# DEPRECATED-lvd.net
KiCad netlist of a schematic drawn in Altium Designer
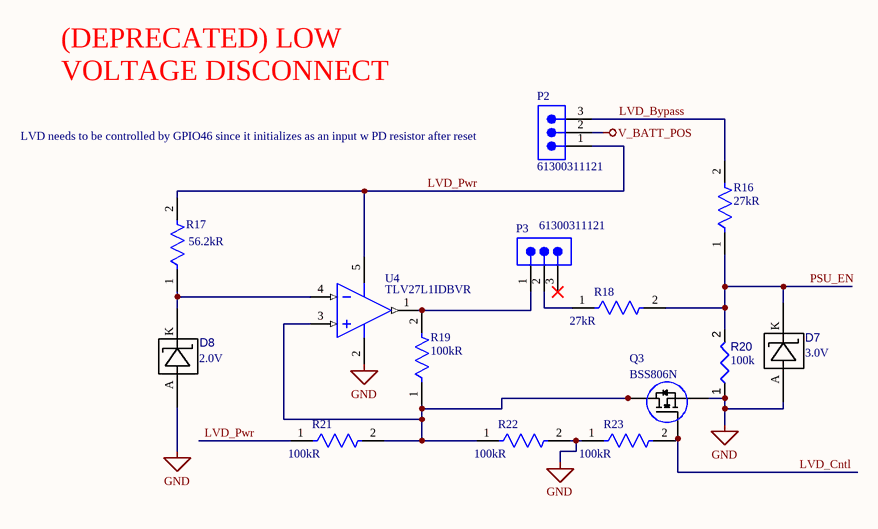
[diagram p0: DEPRECATED-lvd.SchDoc]

(export (version "E")
  (design (tool "Eeschema 10.0.6"))
  (components
    (comp (ref "D7")
      (value "BZX58550-C3V0-QX")
      (footprint "SOD523 (SC-79)")
      (description "Diode Zener Single 3V 5% 300mW 2-Pin SOD-523 T/R")
      (fields (field (name "NOMINAL VOLTAGE") "3.0V"))
      (libsource (lib "Camosun College") (part "Zener - SOD523"))
    )
    (comp (ref "D8")
      (value "BZX58550-C2V0-QX")
      (footprint "SOD523 (SC-79)")
      (description "Diode Zener Single 2V 5% 300mW 2-Pin SOD-523 T/R")
      (fields (field (name "NOMINAL VOLTAGE") "2.0V"))
      (libsource (lib "Camosun College") (part "Zener - SOD523"))
    )
    (comp (ref "P2")
      (value "61300311121")
      (footprint "61300311121")
      (libsource (lib "Camosun College") (part "Header_Male_1R_03P"))
    )
    (comp (ref "P3")
      (value "61300311121")
      (footprint "61300311121")
      (libsource (lib "Camosun College") (part "Header_Male_1R_03P"))
    )
    (comp (ref "Q3")
      (value "BSS806N")
      (footprint "INF-PG-SOT23_M")
      (libsource (lib "Camosun College") (part "MOSFET-N_CHANNEL"))
    )
    (comp (ref "R16")
      (value "RMCF0805FT27K0")
      (footprint "FP-RMCF0805-IPC_A")
      (description "27kΩ ±1% 0.125W 0805 Thick Film Chip Resistor AEC-Q200 compliant")
      (fields (field (name "RESISTANCE") "27kR") (field (name "TOLERANCE") "1%"))
      (libsource (lib "Altium Content Vault") (part "1029c3af85768c4190bb7ad29bc67b5"))
    )
    (comp (ref "R17")
      (value "RMCF0805FT56K2")
      (footprint "FP-RMCF0805-IPC_A")
      (description "56.2kΩ ±1% 0.125W 0805 Thick Film Chip Resistor AEC-Q200 compliant")
      (fields (field (name "TOLERANCE") "1%") (field (name "RESISTANCE") "56.2kR"))
      (libsource (lib "Altium Content Vault") (part "1029c3af85768c4190bb7ad29bc67b5"))
    )
    (comp (ref "R18")
      (value "RMCF0805FT27K0")
      (footprint "FP-RMCF0805-IPC_A")
      (description "27kΩ ±1% 0.125W 0805 Thick Film Chip Resistor AEC-Q200 compliant")
      (fields (field (name "RESISTANCE") "27kR") (field (name "TOLERANCE") "1%"))
      (libsource (lib "Altium Content Vault") (part "1029c3af85768c4190bb7ad29bc67b5"))
    )
    (comp (ref "R19")
      (value "RMCF0805FG100K")
      (footprint "FP-RMCF0805-IPC_C")
      (description "100kΩ ±1% 0.125W 0805 Thick Film Chip Resistor AEC-Q200 compliant")
      (fields (field (name "RESISTANCE") "100kR") (field (name "TOLERANCE") "1%"))
      (libsource (lib "Altium Content Vault") (part "1029c3af85768c4190bb7ad29bc67b5"))
    )
    (comp (ref "R20")
      (value "100k")
      (footprint "RESC1608X55X25ML10T15")
      (description "Chip Resistor, 100 KOhm, +/- 1%, 0.1 W, -55 to 155 degC, 0603 (1608 Metric)")
      (fields (field (name "TOLERANCE") "1%") (field (name "POWER") "100mW"))
      (libsource (lib "Camosun College") (part "RES-2"))
    )
    (comp (ref "R21")
      (value "RMCF0805FG100K")
      (footprint "FP-RMCF0805-IPC_C")
      (description "100kΩ ±1% 0.125W 0805 Thick Film Chip Resistor AEC-Q200 compliant")
      (fields (field (name "RESISTANCE") "100kR") (field (name "TOLERANCE") "1%"))
      (libsource (lib "Altium Content Vault") (part "1029c3af85768c4190bb7ad29bc67b5"))
    )
    (comp (ref "R22")
      (value "RMCF0805FG100K")
      (footprint "FP-RMCF0805-IPC_C")
      (description "100kΩ ±1% 0.125W 0805 Thick Film Chip Resistor AEC-Q200 compliant")
      (fields (field (name "RESISTANCE") "100kR") (field (name "TOLERANCE") "1%"))
      (libsource (lib "Altium Content Vault") (part "1029c3af85768c4190bb7ad29bc67b5"))
    )
    (comp (ref "R23")
      (value "RMCF0805FG100K")
      (footprint "FP-RMCF0805-IPC_C")
      (description "100kΩ ±1% 0.125W 0805 Thick Film Chip Resistor AEC-Q200 compliant")
      (fields (field (name "RESISTANCE") "100kR") (field (name "TOLERANCE") "1%"))
      (libsource (lib "Altium Content Vault") (part "1029c3af85768c4190bb7ad29bc67b5"))
    )
    (comp (ref "U4")
      (value "TLV27L1IDBVR")
      (footprint "DBV0005A_L")
      (fields (field (name "MANUFACTURER") "Texas Instruments"))
      (libsource (lib "Altium Content Vault") (part "TI-TLV2XX1DBV5"))
    )
  )
  (nets
    (net (code "1") (name "/LVD_Bypass") (class "Default")
      (node (ref "P2") (pin "3") (pinfunction "3_3") (pintype "passive"))
      (node (ref "R16") (pin "2") (pinfunction "2_2") (pintype "passive"))
    )
    (net (code "2") (name "/LVD_Cntl") (class "Default")
      (node (ref "Q3") (pin "G") (pinfunction "G_G") (pintype "passive"))
      (node (ref "R23") (pin "2") (pinfunction "2_2") (pintype "passive"))
    )
    (net (code "3") (name "/LVD_Pwr") (class "Default")
      (node (ref "P2") (pin "1") (pinfunction "1_1") (pintype "passive"))
      (node (ref "R17") (pin "2") (pinfunction "2_2") (pintype "passive"))
      (node (ref "R21") (pin "1") (pinfunction "1_1") (pintype "passive"))
      (node (ref "U4") (pin "5") (pinfunction "VDD_5") (pintype "power_in"))
    )
    (net (code "4") (name "/PSU_EN") (class "Default")
      (node (ref "D7") (pin "K") (pinfunction "K_K") (pintype "passive"))
      (node (ref "R16") (pin "1") (pinfunction "1_1") (pintype "passive"))
      (node (ref "R18") (pin "2") (pinfunction "2_2") (pintype "passive"))
      (node (ref "R20") (pin "2") (pinfunction "2_2") (pintype "passive"))
    )
    (net (code "5") (name "GND") (class "Default")
      (node (ref "D7") (pin "A") (pinfunction "A_A") (pintype "passive"))
      (node (ref "D8") (pin "A") (pinfunction "A_A") (pintype "passive"))
      (node (ref "Q3") (pin "S") (pinfunction "S_S") (pintype "passive"))
      (node (ref "R20") (pin "1") (pinfunction "1_1") (pintype "passive"))
      (node (ref "R22") (pin "2") (pinfunction "2_2") (pintype "passive"))
      (node (ref "R23") (pin "1") (pinfunction "1_1") (pintype "passive"))
      (node (ref "U4") (pin "2") (pinfunction "GND_2") (pintype "power_in"))
    )
    (net (code "6") (name "Net-(P3-Pad2)") (class "Default")
      (node (ref "P3") (pin "2") (pinfunction "2_2") (pintype "passive"))
      (node (ref "R18") (pin "1") (pinfunction "1_1") (pintype "passive"))
    )
    (net (code "7") (name "Net-(U4-IN+)") (class "Default")
      (node (ref "Q3") (pin "D") (pinfunction "D_D") (pintype "passive"))
      (node (ref "R19") (pin "1") (pinfunction "1_1") (pintype "passive"))
      (node (ref "R21") (pin "2") (pinfunction "2_2") (pintype "passive"))
      (node (ref "R22") (pin "1") (pinfunction "1_1") (pintype "passive"))
      (node (ref "U4") (pin "3") (pinfunction "IN+_3") (pintype "input"))
    )
    (net (code "8") (name "Net-(U4-IN-)") (class "Default")
      (node (ref "D8") (pin "K") (pinfunction "K_K") (pintype "passive"))
      (node (ref "R17") (pin "1") (pinfunction "1_1") (pintype "passive"))
      (node (ref "U4") (pin "4") (pinfunction "IN-_4") (pintype "input"))
    )
    (net (code "9") (name "Net-(U4-OUT)") (class "Default")
      (node (ref "P3") (pin "1") (pinfunction "1_1") (pintype "passive"))
      (node (ref "R19") (pin "2") (pinfunction "2_2") (pintype "passive"))
      (node (ref "U4") (pin "1") (pinfunction "OUT_1") (pintype "output"))
    )
    (net (code "10") (name "V_BATT_POS") (class "Default")
      (node (ref "P2") (pin "2") (pinfunction "2_2") (pintype "passive"))
    )
    (net (code "11") (name "unconnected-(P3-Pad3)") (class "Default")
      (node (ref "P3") (pin "3") (pinfunction "3_3") (pintype "passive+no_connect"))
    )
  )
)
